# ADC.net
KiCad netlist of a schematic drawn in Altium Designer
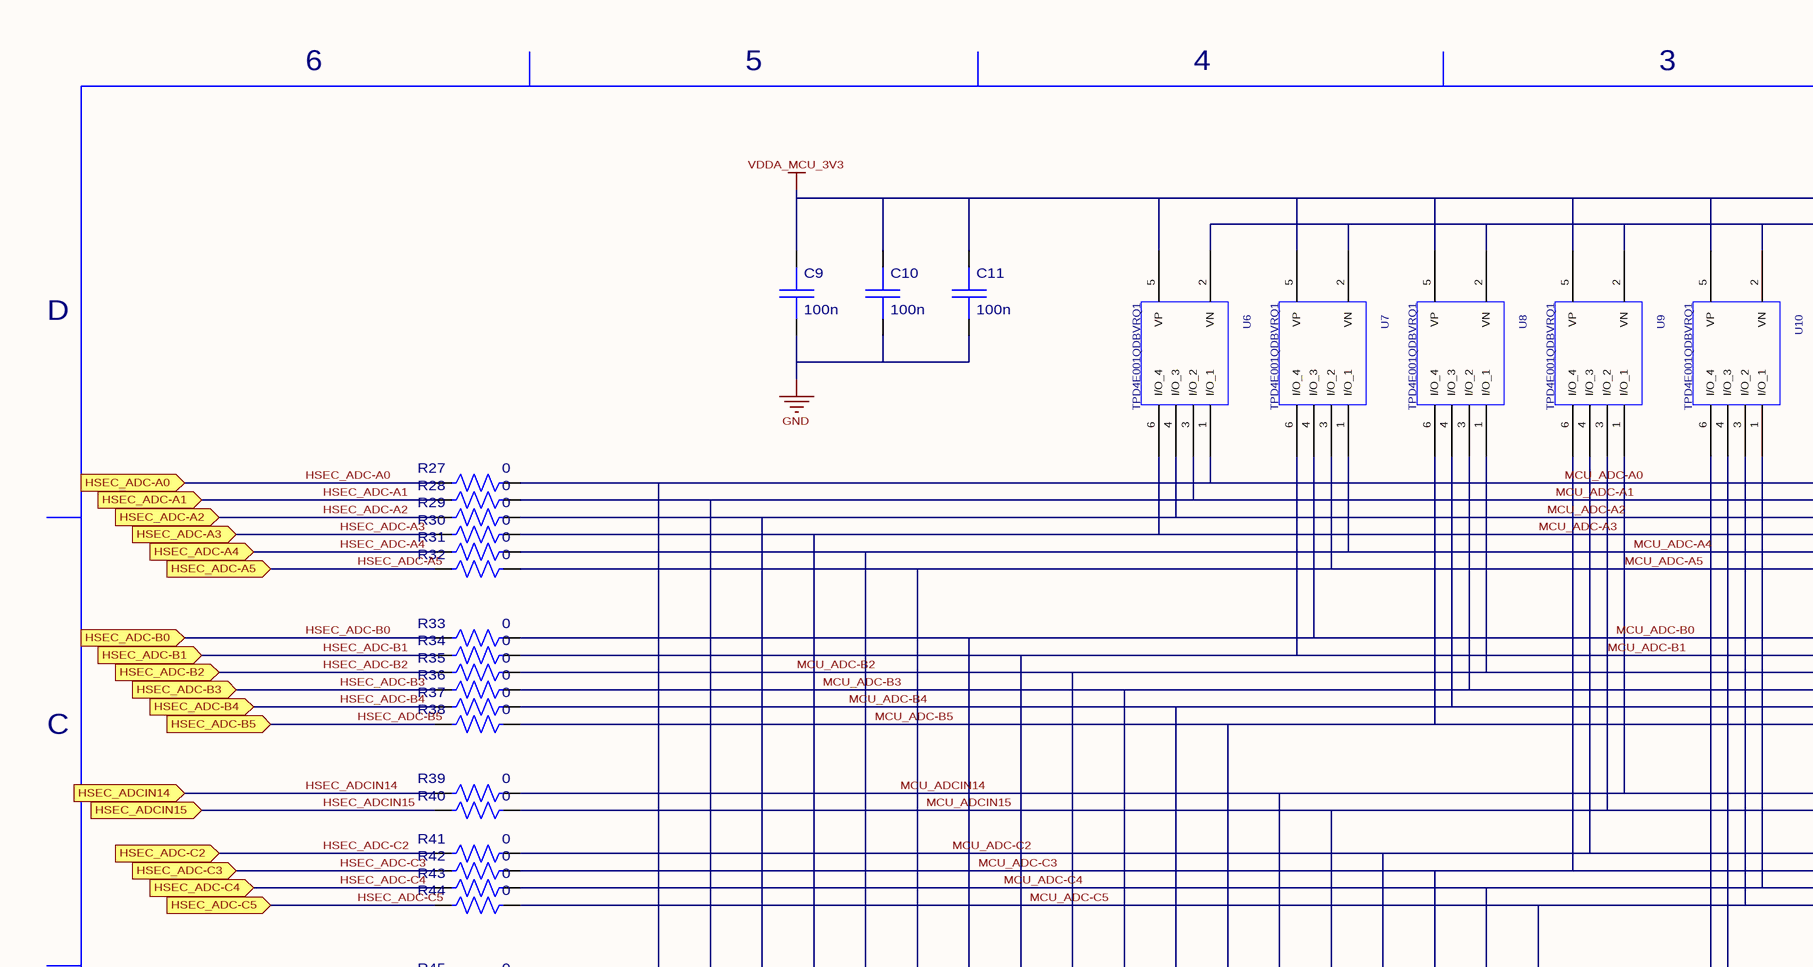
[diagram p0: ADC.SchDoc, top left]
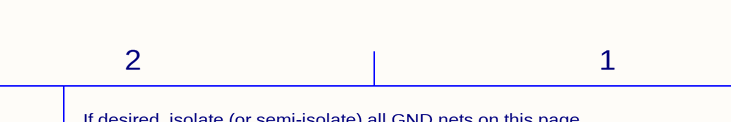
[diagram p1: ADC.SchDoc, top right]
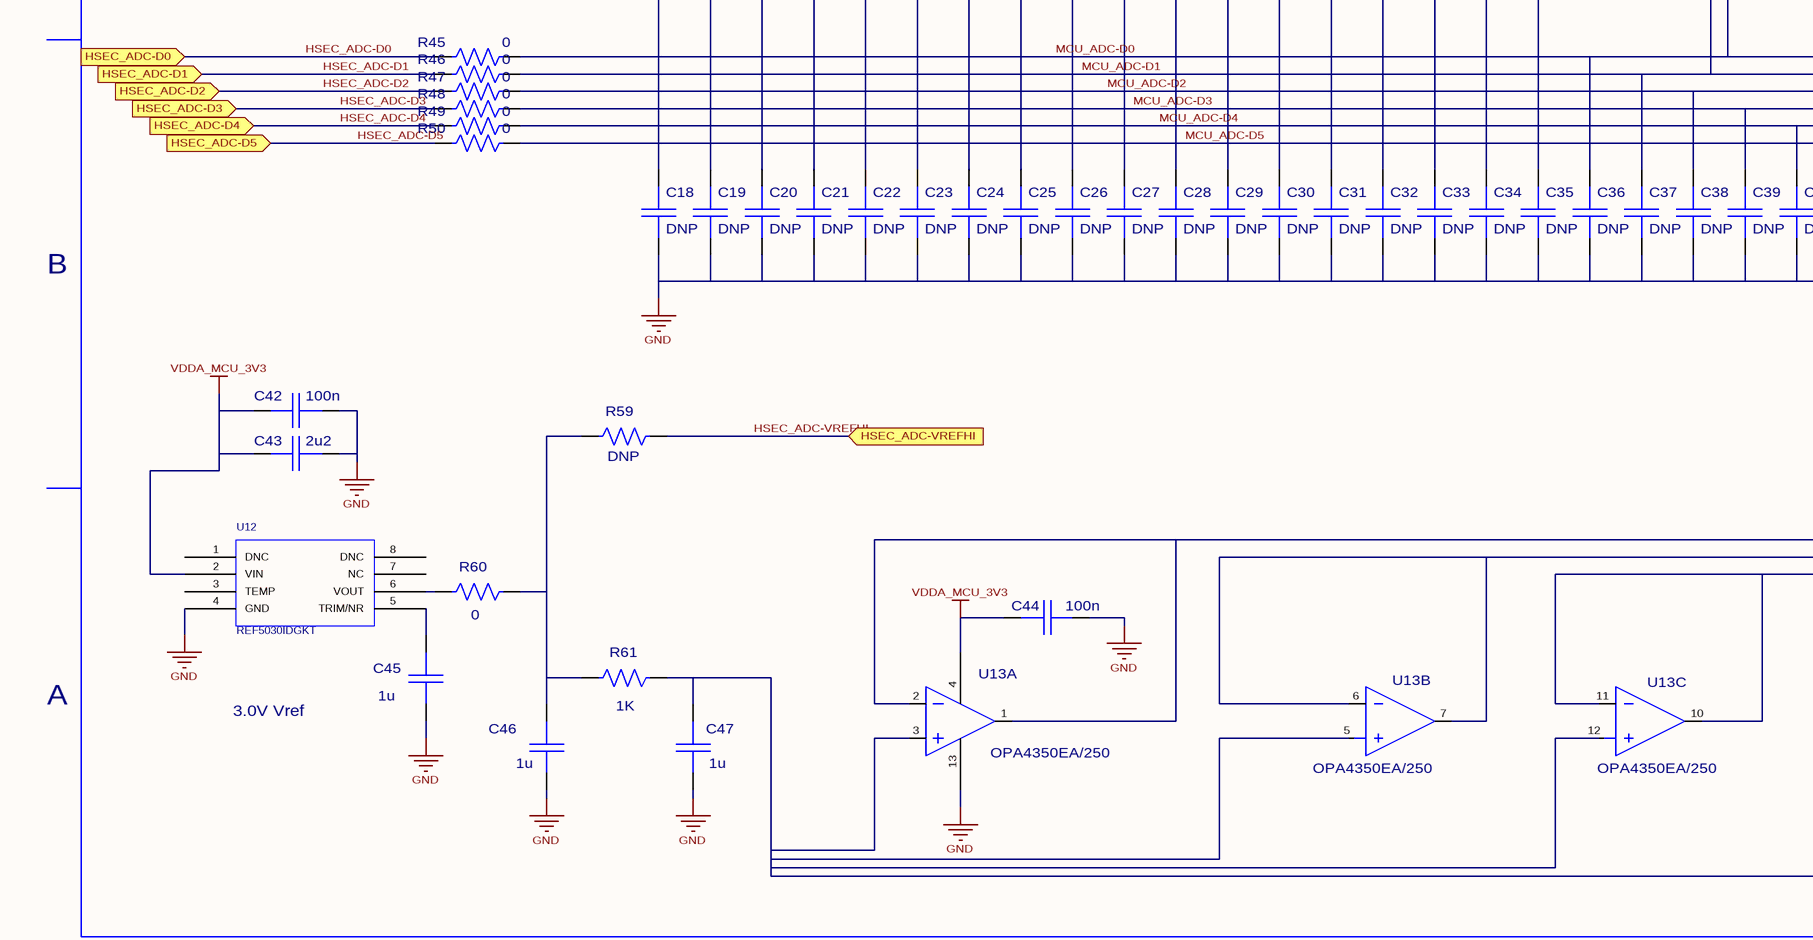
[diagram p2: ADC.SchDoc, bottom left]
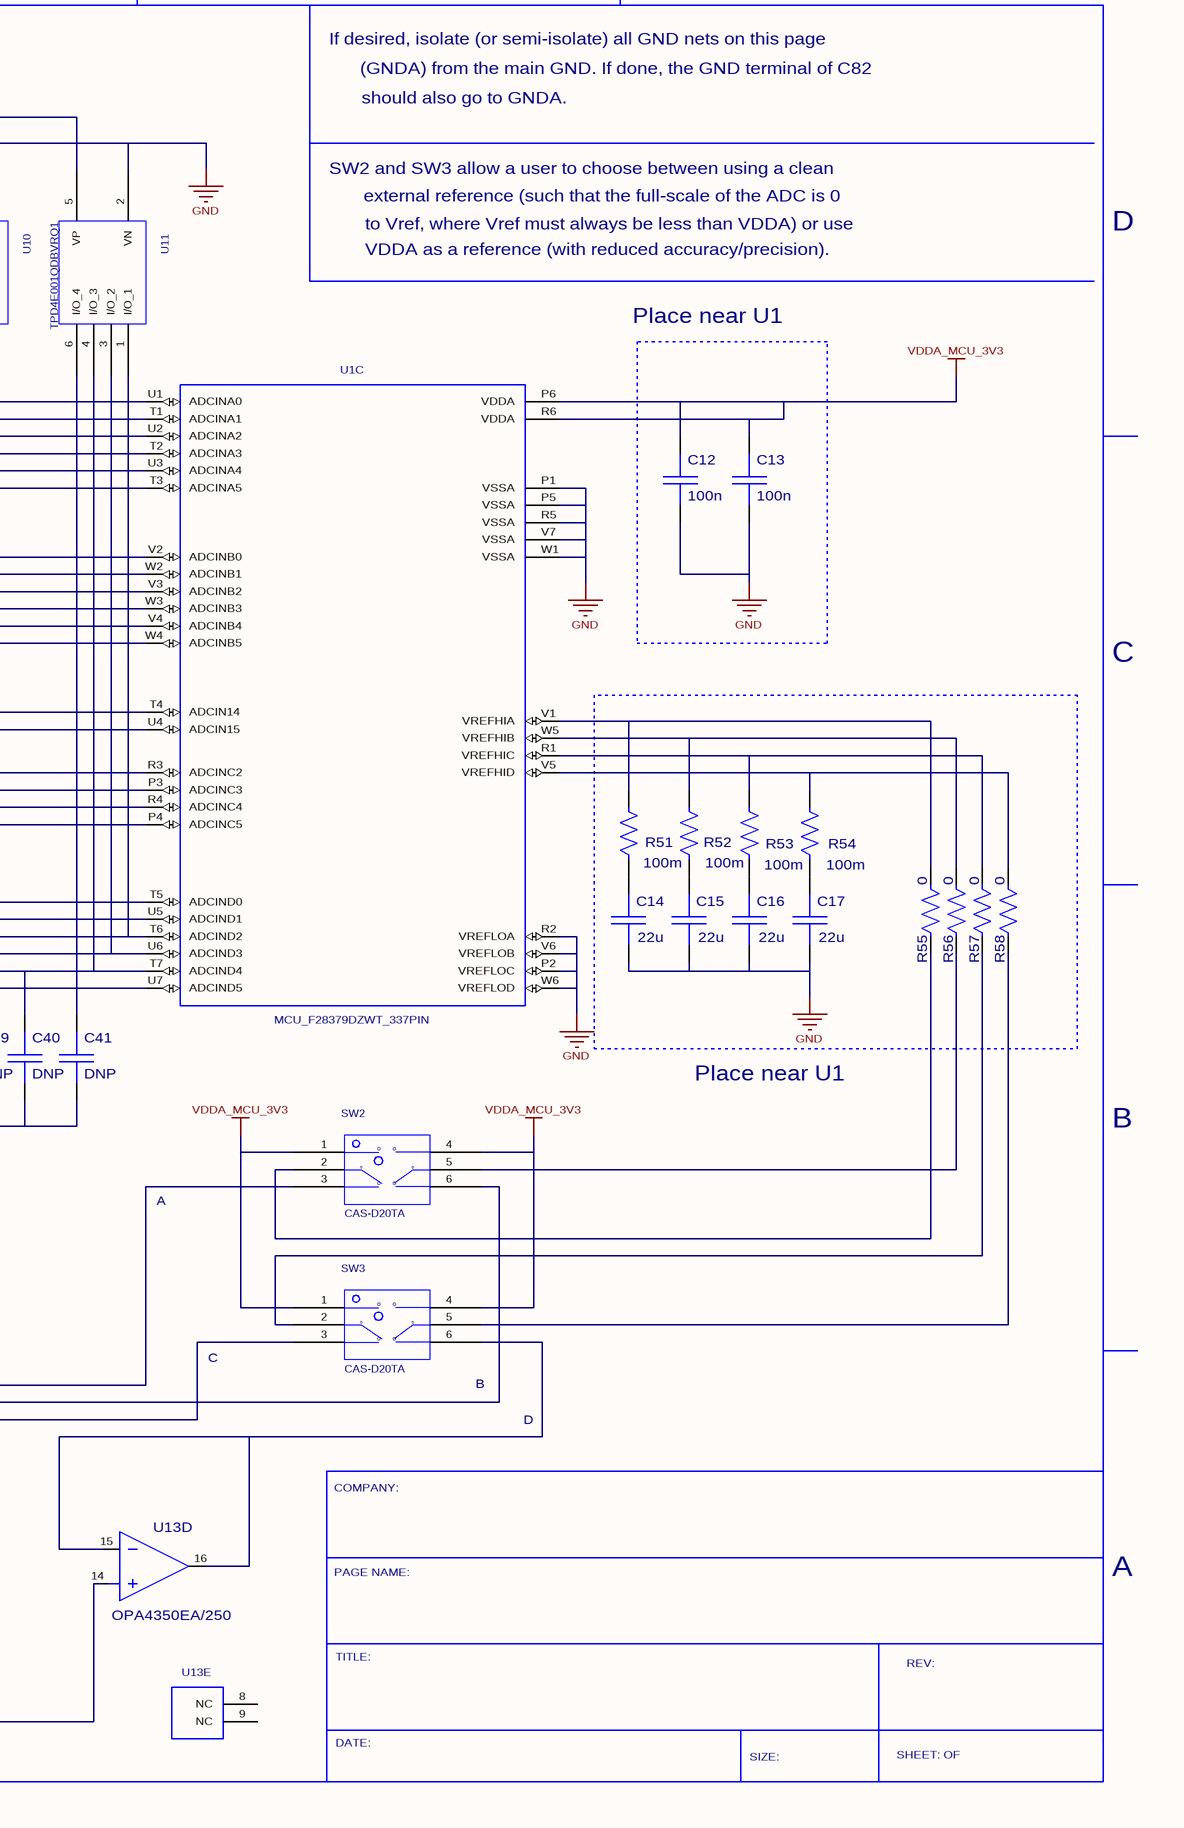
[diagram p3: ADC.SchDoc, bottom right]

(export (version "E")
  (design (tool "Eeschema 10.0.6"))
  (components
    (comp (ref "C9")
      (value "100n")
      (footprint "C0402")
      (description "CAP CER 16V 10% X7R 0402")
      (fields (field (name "Comment") "C0402_16V_X7R"))
      (libsource (lib "*") (part "C0402_16V_X7R"))
    )
    (comp (ref "C10")
      (value "100n")
      (footprint "C0402")
      (description "CAP CER 16V 10% X7R 0402")
      (fields (field (name "Comment") "C0402_16V_X7R"))
      (libsource (lib "*") (part "C0402_16V_X7R"))
    )
    (comp (ref "C11")
      (value "100n")
      (footprint "C0402")
      (description "CAP CER 16V 10% X7R 0402")
      (fields (field (name "Comment") "C0402_16V_X7R"))
      (libsource (lib "*") (part "C0402_16V_X7R"))
    )
    (comp (ref "C12")
      (value "100n")
      (footprint "C0402")
      (description "CAP CER 16V 10% X7R 0402")
      (fields (field (name "Comment") "C0402_16V_X7R"))
      (libsource (lib "*") (part "C0402_16V_X7R"))
    )
    (comp (ref "C13")
      (value "100n")
      (footprint "C0402")
      (description "CAP CER 16V 10% X7R 0402")
      (fields (field (name "Comment") "C0402_16V_X7R"))
      (libsource (lib "*") (part "C0402_16V_X7R"))
    )
    (comp (ref "C14")
      (value "22u")
      (footprint "C0805")
      (description "CAP CER 10V 20% X5R/X7S 0805")
      (fields (field (name "Comment") "C0805_16V_X7R"))
      (libsource (lib "*") (part "C0805_16V_X7R"))
    )
    (comp (ref "C15")
      (value "22u")
      (footprint "C0805")
      (description "CAP CER 10V 20% X5R/X7S 0805")
      (fields (field (name "Comment") "C0805_16V_X7R"))
      (libsource (lib "*") (part "C0805_16V_X7R"))
    )
    (comp (ref "C16")
      (value "22u")
      (footprint "C0805")
      (description "CAP CER 10V 20% X5R/X7S 0805")
      (fields (field (name "Comment") "C0805_16V_X7R"))
      (libsource (lib "*") (part "C0805_16V_X7R"))
    )
    (comp (ref "C17")
      (value "22u")
      (footprint "C0805")
      (description "CAP CER 10V 20% X5R/X7S 0805")
      (fields (field (name "Comment") "C0805_16V_X7R"))
      (libsource (lib "*") (part "C0805_16V_X7R"))
    )
    (comp (ref "C18")
      (value "DNP")
      (footprint "C0603")
      (description "CAP CER 16V 10% X7R 0603")
      (fields (field (name "Comment") "C0603_16V_X7R"))
      (libsource (lib "*") (part "C0603_16V_X7R"))
    )
    (comp (ref "C19")
      (value "DNP")
      (footprint "C0603")
      (description "CAP CER 16V 10% X7R 0603")
      (fields (field (name "Comment") "C0603_16V_X7R"))
      (libsource (lib "*") (part "C0603_16V_X7R"))
    )
    (comp (ref "C20")
      (value "DNP")
      (footprint "C0603")
      (description "CAP CER 16V 10% X7R 0603")
      (fields (field (name "Comment") "C0603_16V_X7R"))
      (libsource (lib "*") (part "C0603_16V_X7R"))
    )
    (comp (ref "C21")
      (value "DNP")
      (footprint "C0603")
      (description "CAP CER 16V 10% X7R 0603")
      (fields (field (name "Comment") "C0603_16V_X7R"))
      (libsource (lib "*") (part "C0603_16V_X7R"))
    )
    (comp (ref "C22")
      (value "DNP")
      (footprint "C0603")
      (description "CAP CER 16V 10% X7R 0603")
      (fields (field (name "Comment") "C0603_16V_X7R"))
      (libsource (lib "*") (part "C0603_16V_X7R"))
    )
    (comp (ref "C23")
      (value "DNP")
      (footprint "C0603")
      (description "CAP CER 16V 10% X7R 0603")
      (fields (field (name "Comment") "C0603_16V_X7R"))
      (libsource (lib "*") (part "C0603_16V_X7R"))
    )
    (comp (ref "C24")
      (value "DNP")
      (footprint "C0603")
      (description "CAP CER 16V 10% X7R 0603")
      (fields (field (name "Comment") "C0603_16V_X7R"))
      (libsource (lib "*") (part "C0603_16V_X7R"))
    )
    (comp (ref "C25")
      (value "DNP")
      (footprint "C0603")
      (description "CAP CER 16V 10% X7R 0603")
      (fields (field (name "Comment") "C0603_16V_X7R"))
      (libsource (lib "*") (part "C0603_16V_X7R"))
    )
    (comp (ref "C26")
      (value "DNP")
      (footprint "C0603")
      (description "CAP CER 16V 10% X7R 0603")
      (fields (field (name "Comment") "C0603_16V_X7R"))
      (libsource (lib "*") (part "C0603_16V_X7R"))
    )
    (comp (ref "C27")
      (value "DNP")
      (footprint "C0603")
      (description "CAP CER 16V 10% X7R 0603")
      (fields (field (name "Comment") "C0603_16V_X7R"))
      (libsource (lib "*") (part "C0603_16V_X7R"))
    )
    (comp (ref "C28")
      (value "DNP")
      (footprint "C0603")
      (description "CAP CER 16V 10% X7R 0603")
      (fields (field (name "Comment") "C0603_16V_X7R"))
      (libsource (lib "*") (part "C0603_16V_X7R"))
    )
    (comp (ref "C29")
      (value "DNP")
      (footprint "C0603")
      (description "CAP CER 16V 10% X7R 0603")
      (fields (field (name "Comment") "C0603_16V_X7R"))
      (libsource (lib "*") (part "C0603_16V_X7R"))
    )
    (comp (ref "C30")
      (value "DNP")
      (footprint "C0603")
      (description "CAP CER 16V 10% X7R 0603")
      (fields (field (name "Comment") "C0603_16V_X7R"))
      (libsource (lib "*") (part "C0603_16V_X7R"))
    )
    (comp (ref "C31")
      (value "DNP")
      (footprint "C0603")
      (description "CAP CER 16V 10% X7R 0603")
      (fields (field (name "Comment") "C0603_16V_X7R"))
      (libsource (lib "*") (part "C0603_16V_X7R"))
    )
    (comp (ref "C32")
      (value "DNP")
      (footprint "C0603")
      (description "CAP CER 16V 10% X7R 0603")
      (fields (field (name "Comment") "C0603_16V_X7R"))
      (libsource (lib "*") (part "C0603_16V_X7R"))
    )
    (comp (ref "C33")
      (value "DNP")
      (footprint "C0603")
      (description "CAP CER 16V 10% X7R 0603")
      (fields (field (name "Comment") "C0603_16V_X7R"))
      (libsource (lib "*") (part "C0603_16V_X7R"))
    )
    (comp (ref "C34")
      (value "DNP")
      (footprint "C0603")
      (description "CAP CER 16V 10% X7R 0603")
      (fields (field (name "Comment") "C0603_16V_X7R"))
      (libsource (lib "*") (part "C0603_16V_X7R"))
    )
    (comp (ref "C35")
      (value "DNP")
      (footprint "C0603")
      (description "CAP CER 16V 10% X7R 0603")
      (fields (field (name "Comment") "C0603_16V_X7R"))
      (libsource (lib "*") (part "C0603_16V_X7R"))
    )
    (comp (ref "C36")
      (value "DNP")
      (footprint "C0603")
      (description "CAP CER 16V 10% X7R 0603")
      (fields (field (name "Comment") "C0603_16V_X7R"))
      (libsource (lib "*") (part "C0603_16V_X7R"))
    )
    (comp (ref "C37")
      (value "DNP")
      (footprint "C0603")
      (description "CAP CER 16V 10% X7R 0603")
      (fields (field (name "Comment") "C0603_16V_X7R"))
      (libsource (lib "*") (part "C0603_16V_X7R"))
    )
    (comp (ref "C38")
      (value "DNP")
      (footprint "C0603")
      (description "CAP CER 16V 10% X7R 0603")
      (fields (field (name "Comment") "C0603_16V_X7R"))
      (libsource (lib "*") (part "C0603_16V_X7R"))
    )
    (comp (ref "C39")
      (value "DNP")
      (footprint "C0603")
      (description "CAP CER 16V 10% X7R 0603")
      (fields (field (name "Comment") "C0603_16V_X7R"))
      (libsource (lib "*") (part "C0603_16V_X7R"))
    )
    (comp (ref "C40")
      (value "DNP")
      (footprint "C0603")
      (description "CAP CER 16V 10% X7R 0603")
      (fields (field (name "Comment") "C0603_16V_X7R"))
      (libsource (lib "*") (part "C0603_16V_X7R"))
    )
    (comp (ref "C41")
      (value "DNP")
      (footprint "C0603")
      (description "CAP CER 16V 10% X7R 0603")
      (fields (field (name "Comment") "C0603_16V_X7R"))
      (libsource (lib "*") (part "C0603_16V_X7R"))
    )
    (comp (ref "C42")
      (value "100n")
      (footprint "C0402")
      (description "CAP CER 16V 10% X7R 0402")
      (fields (field (name "Comment") "C0402_16V_X7R"))
      (libsource (lib "*") (part "C0402_16V_X7R"))
    )
    (comp (ref "C43")
      (value "2u2")
      (footprint "C0603")
      (description "CAP CER 10V 20% X5R 0603")
      (fields (field (name "Comment") "C0603_16V_X7R"))
      (libsource (lib "*") (part "C0603_16V_X7R"))
    )
    (comp (ref "C44")
      (value "100n")
      (footprint "C0402")
      (description "CAP CER 16V 10% X7R 0402")
      (fields (field (name "Comment") "C0402_16V_X7R"))
      (libsource (lib "*") (part "C0402_16V_X7R"))
    )
    (comp (ref "C45")
      (value "1u")
      (footprint "C0402")
      (description "CAP CER 6.3V 10% X7R 0402")
      (fields (field (name "Comment") "C0402_16V_X7R"))
      (libsource (lib "*") (part "C0402_16V_X7R"))
    )
    (comp (ref "C46")
      (value "1u")
      (footprint "C0402")
      (description "CAP CER 6.3V 10% X7R 0402")
      (fields (field (name "Comment") "C0402_16V_X7R"))
      (libsource (lib "*") (part "C0402_16V_X7R"))
    )
    (comp (ref "C47")
      (value "1u")
      (footprint "C0402")
      (description "CAP CER 6.3V 10% X7R 0402")
      (fields (field (name "Comment") "C0402_16V_X7R"))
      (libsource (lib "*") (part "C0402_16V_X7R"))
    )
    (comp (ref "R27")
      (value "0")
      (footprint "R0603")
      (description "RES 1/10W 5% 0603 SMD")
      (fields (field (name "Comment") "R0603_5%"))
      (libsource (lib "*") (part "R0603_5%"))
    )
    (comp (ref "R28")
      (value "0")
      (footprint "R0603")
      (description "RES 1/10W 5% 0603 SMD")
      (fields (field (name "Comment") "R0603_5%"))
      (libsource (lib "*") (part "R0603_5%"))
    )
    (comp (ref "R29")
      (value "0")
      (footprint "R0603")
      (description "RES 1/10W 5% 0603 SMD")
      (fields (field (name "Comment") "R0603_5%"))
      (libsource (lib "*") (part "R0603_5%"))
    )
    (comp (ref "R30")
      (value "0")
      (footprint "R0603")
      (description "RES 1/10W 5% 0603 SMD")
      (fields (field (name "Comment") "R0603_5%"))
      (libsource (lib "*") (part "R0603_5%"))
    )
    (comp (ref "R31")
      (value "0")
      (footprint "R0603")
      (description "RES 1/10W 5% 0603 SMD")
      (fields (field (name "Comment") "R0603_5%"))
      (libsource (lib "*") (part "R0603_5%"))
    )
    (comp (ref "R32")
      (value "0")
      (footprint "R0603")
      (description "RES 1/10W 5% 0603 SMD")
      (fields (field (name "Comment") "R0603_5%"))
      (libsource (lib "*") (part "R0603_5%"))
    )
    (comp (ref "R33")
      (value "0")
      (footprint "R0603")
      (description "RES 1/10W 5% 0603 SMD")
      (fields (field (name "Comment") "R0603_5%"))
      (libsource (lib "*") (part "R0603_5%"))
    )
    (comp (ref "R34")
      (value "0")
      (footprint "R0603")
      (description "RES 1/10W 5% 0603 SMD")
      (fields (field (name "Comment") "R0603_5%"))
      (libsource (lib "*") (part "R0603_5%"))
    )
    (comp (ref "R35")
      (value "0")
      (footprint "R0603")
      (description "RES 1/10W 5% 0603 SMD")
      (fields (field (name "Comment") "R0603_5%"))
      (libsource (lib "*") (part "R0603_5%"))
    )
    (comp (ref "R36")
      (value "0")
      (footprint "R0603")
      (description "RES 1/10W 5% 0603 SMD")
      (fields (field (name "Comment") "R0603_5%"))
      (libsource (lib "*") (part "R0603_5%"))
    )
    (comp (ref "R37")
      (value "0")
      (footprint "R0603")
      (description "RES 1/10W 5% 0603 SMD")
      (fields (field (name "Comment") "R0603_5%"))
      (libsource (lib "*") (part "R0603_5%"))
    )
    (comp (ref "R38")
      (value "0")
      (footprint "R0603")
      (description "RES 1/10W 5% 0603 SMD")
      (fields (field (name "Comment") "R0603_5%"))
      (libsource (lib "*") (part "R0603_5%"))
    )
    (comp (ref "R39")
      (value "0")
      (footprint "R0603")
      (description "RES 1/10W 5% 0603 SMD")
      (fields (field (name "Comment") "R0603_5%"))
      (libsource (lib "*") (part "R0603_5%"))
    )
    (comp (ref "R40")
      (value "0")
      (footprint "R0603")
      (description "RES 1/10W 5% 0603 SMD")
      (fields (field (name "Comment") "R0603_5%"))
      (libsource (lib "*") (part "R0603_5%"))
    )
    (comp (ref "R41")
      (value "0")
      (footprint "R0603")
      (description "RES 1/10W 5% 0603 SMD")
      (fields (field (name "Comment") "R0603_5%"))
      (libsource (lib "*") (part "R0603_5%"))
    )
    (comp (ref "R42")
      (value "0")
      (footprint "R0603")
      (description "RES 1/10W 5% 0603 SMD")
      (fields (field (name "Comment") "R0603_5%"))
      (libsource (lib "*") (part "R0603_5%"))
    )
    (comp (ref "R43")
      (value "0")
      (footprint "R0603")
      (description "RES 1/10W 5% 0603 SMD")
      (fields (field (name "Comment") "R0603_5%"))
      (libsource (lib "*") (part "R0603_5%"))
    )
    (comp (ref "R44")
      (value "0")
      (footprint "R0603")
      (description "RES 1/10W 5% 0603 SMD")
      (fields (field (name "Comment") "R0603_5%"))
      (libsource (lib "*") (part "R0603_5%"))
    )
    (comp (ref "R45")
      (value "0")
      (footprint "R0603")
      (description "RES 1/10W 5% 0603 SMD")
      (fields (field (name "Comment") "R0603_5%"))
      (libsource (lib "*") (part "R0603_5%"))
    )
    (comp (ref "R46")
      (value "0")
      (footprint "R0603")
      (description "RES 1/10W 5% 0603 SMD")
      (fields (field (name "Comment") "R0603_5%"))
      (libsource (lib "*") (part "R0603_5%"))
    )
    (comp (ref "R47")
      (value "0")
      (footprint "R0603")
      (description "RES 1/10W 5% 0603 SMD")
      (fields (field (name "Comment") "R0603_5%"))
      (libsource (lib "*") (part "R0603_5%"))
    )
    (comp (ref "R48")
      (value "0")
      (footprint "R0603")
      (description "RES 1/10W 5% 0603 SMD")
      (fields (field (name "Comment") "R0603_5%"))
      (libsource (lib "*") (part "R0603_5%"))
    )
    (comp (ref "R49")
      (value "0")
      (footprint "R0603")
      (description "RES 1/10W 5% 0603 SMD")
      (fields (field (name "Comment") "R0603_5%"))
      (libsource (lib "*") (part "R0603_5%"))
    )
    (comp (ref "R50")
      (value "0")
      (footprint "R0603")
      (description "RES 1/10W 5% 0603 SMD")
      (fields (field (name "Comment") "R0603_5%"))
      (libsource (lib "*") (part "R0603_5%"))
    )
    (comp (ref "R51")
      (value "100m")
      (footprint "R0603")
      (description "RES 1/10W 5% 0603 SMD")
      (fields (field (name "Comment") "R0603_5%"))
      (libsource (lib "*") (part "R0603_5%"))
    )
    (comp (ref "R52")
      (value "100m")
      (footprint "R0603")
      (description "RES 1/10W 5% 0603 SMD")
      (fields (field (name "Comment") "R0603_5%"))
      (libsource (lib "*") (part "R0603_5%"))
    )
    (comp (ref "R53")
      (value "100m")
      (footprint "R0603")
      (description "RES 1/10W 5% 0603 SMD")
      (fields (field (name "Comment") "R0603_5%"))
      (libsource (lib "*") (part "R0603_5%"))
    )
    (comp (ref "R54")
      (value "100m")
      (footprint "R0603")
      (description "RES 1/10W 5% 0603 SMD")
      (fields (field (name "Comment") "R0603_5%"))
      (libsource (lib "*") (part "R0603_5%"))
    )
    (comp (ref "R55")
      (value "0")
      (footprint "R0402")
      (description "RES 1/16W 5% 0402 SMD")
      (fields (field (name "Comment") "R0402_5%"))
      (libsource (lib "*") (part "R0402_5%"))
    )
    (comp (ref "R56")
      (value "0")
      (footprint "R0402")
      (description "RES 1/16W 5% 0402 SMD")
      (fields (field (name "Comment") "R0402_5%"))
      (libsource (lib "*") (part "R0402_5%"))
    )
    (comp (ref "R57")
      (value "0")
      (footprint "R0402")
      (description "RES 1/16W 5% 0402 SMD")
      (fields (field (name "Comment") "R0402_5%"))
      (libsource (lib "*") (part "R0402_5%"))
    )
    (comp (ref "R58")
      (value "0")
      (footprint "R0402")
      (description "RES 1/16W 5% 0402 SMD")
      (fields (field (name "Comment") "R0402_5%"))
      (libsource (lib "*") (part "R0402_5%"))
    )
    (comp (ref "R59")
      (value "DNP")
      (footprint "R0603")
      (description "RES 1/10W 5% 0603 SMD")
      (fields (field (name "Comment") "R0603_5%"))
      (libsource (lib "*") (part "R0603_5%"))
    )
    (comp (ref "R60")
      (value "0")
      (footprint "R0603")
      (description "RES 1/10W 5% 0603 SMD")
      (fields (field (name "Comment") "R0603_5%"))
      (libsource (lib "*") (part "R0603_5%"))
    )
    (comp (ref "R61")
      (value "1K")
      (footprint "R0603")
      (description "RES 1/10W 5% 0603 SMD")
      (fields (field (name "Comment") "R0603_5%"))
      (libsource (lib "*") (part "R0603_5%"))
    )
    (comp (ref "SW2")
      (value "CAS-D20TA")
      (footprint "SWITCH_CAS-D20TA")
      (description "Switch SPDT, 2 position")
      (fields (field (name "MANUFACTURER") "Copal Electronics") (field (name "Comment") "SWITCH_CAS-D20TA"))
      (libsource (lib "*") (part "SWITCH_CAS-D20TA"))
    )
    (comp (ref "SW3")
      (value "CAS-D20TA")
      (footprint "SWITCH_CAS-D20TA")
      (description "Switch SPDT, 2 position")
      (fields (field (name "MANUFACTURER") "Copal Electronics") (field (name "Comment") "SWITCH_CAS-D20TA"))
      (libsource (lib "*") (part "SWITCH_CAS-D20TA"))
    )
    (comp (ref "U1")
      (value "MCU_F28379DZWT_337PIN")
      (footprint "TI_ZWT_337BGA")
      (description "MCU F2837x 337pin ZWT BGA")
      (fields (field (name "PART NUMBER") "TMS320F28379DZWT"))
      (libsource (lib "*") (part "MCU_F28379DZWT_337PIN"))
    )
    (comp (ref "U6")
      (value "TPD4E001QDBVRQ1")
      (footprint "SOT-23-6")
      (description "TVS 4-ch UniDir Diode Array: VCC & GND prot, 11V brkdwn")
      (fields (field (name "MANUFACTURER") "Texas Instruments"))
      (libsource (lib "*") (part "TPD4E001QDBVRQ1"))
    )
    (comp (ref "U7")
      (value "TPD4E001QDBVRQ1")
      (footprint "SOT-23-6")
      (description "TVS 4-ch UniDir Diode Array: VCC & GND prot, 11V brkdwn")
      (fields (field (name "MANUFACTURER") "Texas Instruments"))
      (libsource (lib "*") (part "TPD4E001QDBVRQ1"))
    )
    (comp (ref "U8")
      (value "TPD4E001QDBVRQ1")
      (footprint "SOT-23-6")
      (description "TVS 4-ch UniDir Diode Array: VCC & GND prot, 11V brkdwn")
      (fields (field (name "MANUFACTURER") "Texas Instruments"))
      (libsource (lib "*") (part "TPD4E001QDBVRQ1"))
    )
    (comp (ref "U9")
      (value "TPD4E001QDBVRQ1")
      (footprint "SOT-23-6")
      (description "TVS 4-ch UniDir Diode Array: VCC & GND prot, 11V brkdwn")
      (fields (field (name "MANUFACTURER") "Texas Instruments"))
      (libsource (lib "*") (part "TPD4E001QDBVRQ1"))
    )
    (comp (ref "U10")
      (value "TPD4E001QDBVRQ1")
      (footprint "SOT-23-6")
      (description "TVS 4-ch UniDir Diode Array: VCC & GND prot, 11V brkdwn")
      (fields (field (name "MANUFACTURER") "Texas Instruments"))
      (libsource (lib "*") (part "TPD4E001QDBVRQ1"))
    )
    (comp (ref "U11")
      (value "TPD4E001QDBVRQ1")
      (footprint "SOT-23-6")
      (description "TVS 4-ch UniDir Diode Array: VCC & GND prot, 11V brkdwn")
      (fields (field (name "MANUFACTURER") "Texas Instruments"))
      (libsource (lib "*") (part "TPD4E001QDBVRQ1"))
    )
    (comp (ref "U12")
      (value "REF5030IDGKT")
      (footprint "MSOP8_DGK")
      (description "IC, 3.0V Vref, 0.05%, 8DGK")
      (fields (field (name "Comment") "IC_REF_REF5030IDGK"))
      (libsource (lib "*") (part "IC_REF_REF5030IDGK"))
    )
    (comp (ref "U13")
      (value "OPA4350EA/250")
      (footprint "SSOP16_DBQ")
      (description "IC OPAMP GP R-R 38MHZ QUAD 16DBQ")
      (fields (field (name "PART NUMBER") "OPA4350EA/250") (field (name "Comment") "IC_OPA_OPA4350EA"))
      (libsource (lib "*") (part "IC_OPA_OPA4350EA"))
    )
  )
  (nets
    (net (code "1") (name "/HSEC_ADC-A0") (class "Default")
      (node (ref "R27") (pin "1") (pinfunction "1_1") (pintype "passive"))
    )
    (net (code "2") (name "/HSEC_ADC-A1") (class "Default")
      (node (ref "R28") (pin "1") (pinfunction "1_1") (pintype "passive"))
    )
    (net (code "3") (name "/HSEC_ADC-A2") (class "Default")
      (node (ref "R29") (pin "1") (pinfunction "1_1") (pintype "passive"))
    )
    (net (code "4") (name "/HSEC_ADC-A3") (class "Default")
      (node (ref "R30") (pin "1") (pinfunction "1_1") (pintype "passive"))
    )
    (net (code "5") (name "/HSEC_ADC-A4") (class "Default")
      (node (ref "R31") (pin "1") (pinfunction "1_1") (pintype "passive"))
    )
    (net (code "6") (name "/HSEC_ADC-A5") (class "Default")
      (node (ref "R32") (pin "1") (pinfunction "1_1") (pintype "passive"))
    )
    (net (code "7") (name "/HSEC_ADC-B0") (class "Default")
      (node (ref "R33") (pin "1") (pinfunction "1_1") (pintype "passive"))
    )
    (net (code "8") (name "/HSEC_ADC-B1") (class "Default")
      (node (ref "R34") (pin "1") (pinfunction "1_1") (pintype "passive"))
    )
    (net (code "9") (name "/HSEC_ADC-B2") (class "Default")
      (node (ref "R35") (pin "1") (pinfunction "1_1") (pintype "passive"))
    )
    (net (code "10") (name "/HSEC_ADC-B3") (class "Default")
      (node (ref "R36") (pin "1") (pinfunction "1_1") (pintype "passive"))
    )
    (net (code "11") (name "/HSEC_ADC-B4") (class "Default")
      (node (ref "R37") (pin "1") (pinfunction "1_1") (pintype "passive"))
    )
    (net (code "12") (name "/HSEC_ADC-B5") (class "Default")
      (node (ref "R38") (pin "1") (pinfunction "1_1") (pintype "passive"))
    )
    (net (code "13") (name "/HSEC_ADC-C2") (class "Default")
      (node (ref "R41") (pin "1") (pinfunction "1_1") (pintype "passive"))
    )
    (net (code "14") (name "/HSEC_ADC-C3") (class "Default")
      (node (ref "R42") (pin "1") (pinfunction "1_1") (pintype "passive"))
    )
    (net (code "15") (name "/HSEC_ADC-C4") (class "Default")
      (node (ref "R43") (pin "1") (pinfunction "1_1") (pintype "passive"))
    )
    (net (code "16") (name "/HSEC_ADC-C5") (class "Default")
      (node (ref "R44") (pin "1") (pinfunction "1_1") (pintype "passive"))
    )
    (net (code "17") (name "/HSEC_ADC-D0") (class "Default")
      (node (ref "R45") (pin "1") (pinfunction "1_1") (pintype "passive"))
    )
    (net (code "18") (name "/HSEC_ADC-D1") (class "Default")
      (node (ref "R46") (pin "1") (pinfunction "1_1") (pintype "passive"))
    )
    (net (code "19") (name "/HSEC_ADC-D2") (class "Default")
      (node (ref "R47") (pin "1") (pinfunction "1_1") (pintype "passive"))
    )
    (net (code "20") (name "/HSEC_ADC-D3") (class "Default")
      (node (ref "R48") (pin "1") (pinfunction "1_1") (pintype "passive"))
    )
    (net (code "21") (name "/HSEC_ADC-D4") (class "Default")
      (node (ref "R49") (pin "1") (pinfunction "1_1") (pintype "passive"))
    )
    (net (code "22") (name "/HSEC_ADC-D5") (class "Default")
      (node (ref "R50") (pin "1") (pinfunction "1_1") (pintype "passive"))
    )
    (net (code "23") (name "/HSEC_ADC-VREFHI") (class "Default")
      (node (ref "R59") (pin "2") (pinfunction "2_2") (pintype "passive"))
    )
    (net (code "24") (name "/HSEC_ADCIN14") (class "Default")
      (node (ref "R39") (pin "1") (pinfunction "1_1") (pintype "passive"))
    )
    (net (code "25") (name "/HSEC_ADCIN15") (class "Default")
      (node (ref "R40") (pin "1") (pinfunction "1_1") (pintype "passive"))
    )
    (net (code "26") (name "/MCU_ADC-A0") (class "Default")
      (node (ref "C18") (pin "2") (pinfunction "2_2") (pintype "passive"))
      (node (ref "R27") (pin "2") (pinfunction "2_2") (pintype "passive"))
      (node (ref "U1") (pin "U1") (pinfunction "ADCINA0_U1") (pintype "bidirectional"))
      (node (ref "U6") (pin "1") (pinfunction "I/O_1_1") (pintype "passive"))
    )
    (net (code "27") (name "/MCU_ADC-A1") (class "Default")
      (node (ref "C19") (pin "2") (pinfunction "2_2") (pintype "passive"))
      (node (ref "R28") (pin "2") (pinfunction "2_2") (pintype "passive"))
      (node (ref "U1") (pin "T1") (pinfunction "ADCINA1_T1") (pintype "bidirectional"))
      (node (ref "U6") (pin "3") (pinfunction "I/O_2_3") (pintype "passive"))
    )
    (net (code "28") (name "/MCU_ADC-A2") (class "Default")
      (node (ref "C20") (pin "2") (pinfunction "2_2") (pintype "passive"))
      (node (ref "R29") (pin "2") (pinfunction "2_2") (pintype "passive"))
      (node (ref "U1") (pin "U2") (pinfunction "ADCINA2_U2") (pintype "bidirectional"))
      (node (ref "U6") (pin "4") (pinfunction "I/O_3_4") (pintype "passive"))
    )
    (net (code "29") (name "/MCU_ADC-A3") (class "Default")
      (node (ref "C21") (pin "2") (pinfunction "2_2") (pintype "passive"))
      (node (ref "R30") (pin "2") (pinfunction "2_2") (pintype "passive"))
      (node (ref "U1") (pin "T2") (pinfunction "ADCINA3_T2") (pintype "bidirectional"))
      (node (ref "U6") (pin "6") (pinfunction "I/O_4_6") (pintype "passive"))
    )
    (net (code "30") (name "/MCU_ADC-A4") (class "Default")
      (node (ref "C22") (pin "2") (pinfunction "2_2") (pintype "passive"))
      (node (ref "R31") (pin "2") (pinfunction "2_2") (pintype "passive"))
      (node (ref "U1") (pin "U3") (pinfunction "ADCINA4_U3") (pintype "bidirectional"))
      (node (ref "U7") (pin "1") (pinfunction "I/O_1_1") (pintype "passive"))
    )
    (net (code "31") (name "/MCU_ADC-A5") (class "Default")
      (node (ref "C23") (pin "2") (pinfunction "2_2") (pintype "passive"))
      (node (ref "C30") (pin "2") (pinfunction "2_2") (pintype "passive"))
      (node (ref "R32") (pin "2") (pinfunction "2_2") (pintype "passive"))
      (node (ref "R39") (pin "2") (pinfunction "2_2") (pintype "passive"))
      (node (ref "U1") (pin "T3") (pinfunction "ADCINA5_T3") (pintype "bidirectional"))
      (node (ref "U1") (pin "T4") (pinfunction "ADCIN14_T4") (pintype "bidirectional"))
      (node (ref "U7") (pin "3") (pinfunction "I/O_2_3") (pintype "passive"))
      (node (ref "U9") (pin "1") (pinfunction "I/O_1_1") (pintype "passive"))
    )
    (net (code "32") (name "/MCU_ADC-B0") (class "Default")
      (node (ref "C24") (pin "2") (pinfunction "2_2") (pintype "passive"))
      (node (ref "R33") (pin "2") (pinfunction "2_2") (pintype "passive"))
      (node (ref "U1") (pin "V2") (pinfunction "ADCINB0_V2") (pintype "bidirectional"))
      (node (ref "U7") (pin "4") (pinfunction "I/O_3_4") (pintype "passive"))
    )
    (net (code "33") (name "/MCU_ADC-B1") (class "Default")
      (node (ref "C25") (pin "2") (pinfunction "2_2") (pintype "passive"))
      (node (ref "C31") (pin "2") (pinfunction "2_2") (pintype "passive"))
      (node (ref "R34") (pin "2") (pinfunction "2_2") (pintype "passive"))
      (node (ref "R40") (pin "2") (pinfunction "2_2") (pintype "passive"))
      (node (ref "U1") (pin "U4") (pinfunction "ADCIN15_U4") (pintype "bidirectional"))
      (node (ref "U1") (pin "W2") (pinfunction "ADCINB1_W2") (pintype "bidirectional"))
      (node (ref "U7") (pin "6") (pinfunction "I/O_4_6") (pintype "passive"))
      (node (ref "U9") (pin "3") (pinfunction "I/O_2_3") (pintype "passive"))
    )
    (net (code "34") (name "/MCU_ADC-B2") (class "Default")
      (node (ref "C26") (pin "2") (pinfunction "2_2") (pintype "passive"))
      (node (ref "R35") (pin "2") (pinfunction "2_2") (pintype "passive"))
      (node (ref "U1") (pin "V3") (pinfunction "ADCINB2_V3") (pintype "bidirectional"))
      (node (ref "U8") (pin "1") (pinfunction "I/O_1_1") (pintype "passive"))
    )
    (net (code "35") (name "/MCU_ADC-B3") (class "Default")
      (node (ref "C27") (pin "2") (pinfunction "2_2") (pintype "passive"))
      (node (ref "R36") (pin "2") (pinfunction "2_2") (pintype "passive"))
      (node (ref "U1") (pin "W3") (pinfunction "ADCINB3_W3") (pintype "bidirectional"))
      (node (ref "U8") (pin "3") (pinfunction "I/O_2_3") (pintype "passive"))
    )
    (net (code "36") (name "/MCU_ADC-B4") (class "Default")
      (node (ref "C28") (pin "2") (pinfunction "2_2") (pintype "passive"))
      (node (ref "R37") (pin "2") (pinfunction "2_2") (pintype "passive"))
      (node (ref "U1") (pin "V4") (pinfunction "ADCINB4_V4") (pintype "bidirectional"))
      (node (ref "U8") (pin "4") (pinfunction "I/O_3_4") (pintype "passive"))
    )
    (net (code "37") (name "/MCU_ADC-B5") (class "Default")
      (node (ref "C29") (pin "2") (pinfunction "2_2") (pintype "passive"))
      (node (ref "R38") (pin "2") (pinfunction "2_2") (pintype "passive"))
      (node (ref "U1") (pin "W4") (pinfunction "ADCINB5_W4") (pintype "bidirectional"))
      (node (ref "U8") (pin "6") (pinfunction "I/O_4_6") (pintype "passive"))
    )
    (net (code "38") (name "/MCU_ADC-C2") (class "Default")
      (node (ref "C32") (pin "2") (pinfunction "2_2") (pintype "passive"))
      (node (ref "R41") (pin "2") (pinfunction "2_2") (pintype "passive"))
      (node (ref "U1") (pin "R3") (pinfunction "ADCINC2_R3") (pintype "bidirectional"))
      (node (ref "U9") (pin "4") (pinfunction "I/O_3_4") (pintype "passive"))
    )
    (net (code "39") (name "/MCU_ADC-C3") (class "Default")
      (node (ref "C33") (pin "2") (pinfunction "2_2") (pintype "passive"))
      (node (ref "R42") (pin "2") (pinfunction "2_2") (pintype "passive"))
      (node (ref "U1") (pin "P3") (pinfunction "ADCINC3_P3") (pintype "bidirectional"))
      (node (ref "U9") (pin "6") (pinfunction "I/O_4_6") (pintype "passive"))
    )
    (net (code "40") (name "/MCU_ADC-C4") (class "Default")
      (node (ref "C34") (pin "2") (pinfunction "2_2") (pintype "passive"))
      (node (ref "R43") (pin "2") (pinfunction "2_2") (pintype "passive"))
      (node (ref "U1") (pin "R4") (pinfunction "ADCINC4_R4") (pintype "bidirectional"))
      (node (ref "U10") (pin "1") (pinfunction "I/O_1_1") (pintype "passive"))
    )
    (net (code "41") (name "/MCU_ADC-C5") (class "Default")
      (node (ref "C35") (pin "2") (pinfunction "2_2") (pintype "passive"))
      (node (ref "R44") (pin "2") (pinfunction "2_2") (pintype "passive"))
      (node (ref "U1") (pin "P4") (pinfunction "ADCINC5_P4") (pintype "bidirectional"))
      (node (ref "U10") (pin "3") (pinfunction "I/O_2_3") (pintype "passive"))
    )
    (net (code "42") (name "/MCU_ADC-D0") (class "Default")
      (node (ref "C36") (pin "2") (pinfunction "2_2") (pintype "passive"))
      (node (ref "R45") (pin "2") (pinfunction "2_2") (pintype "passive"))
      (node (ref "U1") (pin "T5") (pinfunction "ADCIND0_T5") (pintype "bidirectional"))
      (node (ref "U10") (pin "4") (pinfunction "I/O_3_4") (pintype "passive"))
    )
    (net (code "43") (name "/MCU_ADC-D1") (class "Default")
      (node (ref "C37") (pin "2") (pinfunction "2_2") (pintype "passive"))
      (node (ref "R46") (pin "2") (pinfunction "2_2") (pintype "passive"))
      (node (ref "U1") (pin "U5") (pinfunction "ADCIND1_U5") (pintype "bidirectional"))
      (node (ref "U10") (pin "6") (pinfunction "I/O_4_6") (pintype "passive"))
    )
    (net (code "44") (name "/MCU_ADC-D2") (class "Default")
      (node (ref "C38") (pin "2") (pinfunction "2_2") (pintype "passive"))
      (node (ref "R47") (pin "2") (pinfunction "2_2") (pintype "passive"))
      (node (ref "U1") (pin "T6") (pinfunction "ADCIND2_T6") (pintype "bidirectional"))
      (node (ref "U11") (pin "1") (pinfunction "I/O_1_1") (pintype "passive"))
    )
    (net (code "45") (name "/MCU_ADC-D3") (class "Default")
      (node (ref "C39") (pin "2") (pinfunction "2_2") (pintype "passive"))
      (node (ref "R48") (pin "2") (pinfunction "2_2") (pintype "passive"))
      (node (ref "U1") (pin "U6") (pinfunction "ADCIND3_U6") (pintype "bidirectional"))
      (node (ref "U11") (pin "3") (pinfunction "I/O_2_3") (pintype "passive"))
    )
    (net (code "46") (name "/MCU_ADC-D4") (class "Default")
      (node (ref "C40") (pin "2") (pinfunction "2_2") (pintype "passive"))
      (node (ref "R49") (pin "2") (pinfunction "2_2") (pintype "passive"))
      (node (ref "U1") (pin "T7") (pinfunction "ADCIND4_T7") (pintype "bidirectional"))
      (node (ref "U11") (pin "4") (pinfunction "I/O_3_4") (pintype "passive"))
    )
    (net (code "47") (name "/MCU_ADC-D5") (class "Default")
      (node (ref "C41") (pin "2") (pinfunction "2_2") (pintype "passive"))
      (node (ref "R50") (pin "2") (pinfunction "2_2") (pintype "passive"))
      (node (ref "U1") (pin "U7") (pinfunction "ADCIND5_U7") (pintype "bidirectional"))
      (node (ref "U11") (pin "6") (pinfunction "I/O_4_6") (pintype "passive"))
    )
    (net (code "48") (name "GND") (class "Default")
      (node (ref "C10") (pin "1") (pinfunction "1_1") (pintype "passive"))
      (node (ref "C11") (pin "1") (pinfunction "1_1") (pintype "passive"))
      (node (ref "C12") (pin "1") (pinfunction "1_1") (pintype "passive"))
      (node (ref "C13") (pin "1") (pinfunction "1_1") (pintype "passive"))
      (node (ref "C14") (pin "1") (pinfunction "1_1") (pintype "passive"))
      (node (ref "C15") (pin "1") (pinfunction "1_1") (pintype "passive"))
      (node (ref "C16") (pin "1") (pinfunction "1_1") (pintype "passive"))
      (node (ref "C17") (pin "1") (pinfunction "1_1") (pintype "passive"))
      (node (ref "C18") (pin "1") (pinfunction "1_1") (pintype "passive"))
      (node (ref "C19") (pin "1") (pinfunction "1_1") (pintype "passive"))
      (node (ref "C20") (pin "1") (pinfunction "1_1") (pintype "passive"))
      (node (ref "C21") (pin "1") (pinfunction "1_1") (pintype "passive"))
      (node (ref "C22") (pin "1") (pinfunction "1_1") (pintype "passive"))
      (node (ref "C23") (pin "1") (pinfunction "1_1") (pintype "passive"))
      (node (ref "C24") (pin "1") (pinfunction "1_1") (pintype "passive"))
      (node (ref "C25") (pin "1") (pinfunction "1_1") (pintype "passive"))
      (node (ref "C26") (pin "1") (pinfunction "1_1") (pintype "passive"))
      (node (ref "C27") (pin "1") (pinfunction "1_1") (pintype "passive"))
      (node (ref "C28") (pin "1") (pinfunction "1_1") (pintype "passive"))
      (node (ref "C29") (pin "1") (pinfunction "1_1") (pintype "passive"))
      (node (ref "C30") (pin "1") (pinfunction "1_1") (pintype "passive"))
      (node (ref "C31") (pin "1") (pinfunction "1_1") (pintype "passive"))
      (node (ref "C32") (pin "1") (pinfunction "1_1") (pintype "passive"))
      (node (ref "C33") (pin "1") (pinfunction "1_1") (pintype "passive"))
      (node (ref "C34") (pin "1") (pinfunction "1_1") (pintype "passive"))
      (node (ref "C35") (pin "1") (pinfunction "1_1") (pintype "passive"))
      (node (ref "C36") (pin "1") (pinfunction "1_1") (pintype "passive"))
      (node (ref "C37") (pin "1") (pinfunction "1_1") (pintype "passive"))
      (node (ref "C38") (pin "1") (pinfunction "1_1") (pintype "passive"))
      (node (ref "C39") (pin "1") (pinfunction "1_1") (pintype "passive"))
      (node (ref "C40") (pin "1") (pinfunction "1_1") (pintype "passive"))
      (node (ref "C41") (pin "1") (pinfunction "1_1") (pintype "passive"))
      (node (ref "C42") (pin "2") (pinfunction "2_2") (pintype "passive"))
      (node (ref "C43") (pin "2") (pinfunction "2_2") (pintype "passive"))
      (node (ref "C44") (pin "1") (pinfunction "1_1") (pintype "passive"))
      (node (ref "C45") (pin "1") (pinfunction "1_1") (pintype "passive"))
      (node (ref "C46") (pin "1") (pinfunction "1_1") (pintype "passive"))
      (node (ref "C47") (pin "1") (pinfunction "1_1") (pintype "passive"))
      (node (ref "C9") (pin "1") (pinfunction "1_1") (pintype "passive"))
      (node (ref "U1") (pin "P1") (pinfunction "VSSA_P1") (pintype "passive"))
      (node (ref "U1") (pin "P2") (pinfunction "VREFLOC_P2") (pintype "bidirectional"))
      (node (ref "U1") (pin "P5") (pinfunction "VSSA_P5") (pintype "passive"))
      (node (ref "U1") (pin "R2") (pinfunction "VREFLOA_R2") (pintype "bidirectional"))
      (node (ref "U1") (pin "R5") (pinfunction "VSSA_R5") (pintype "passive"))
      (node (ref "U1") (pin "V6") (pinfunction "VREFLOB_V6") (pintype "bidirectional"))
      (node (ref "U1") (pin "V7") (pinfunction "VSSA_V7") (pintype "passive"))
      (node (ref "U1") (pin "W1") (pinfunction "VSSA_W1") (pintype "passive"))
      (node (ref "U1") (pin "W6") (pinfunction "VREFLOD_W6") (pintype "bidirectional"))
      (node (ref "U10") (pin "2") (pinfunction "VN_2") (pintype "power_in"))
      (node (ref "U11") (pin "2") (pinfunction "VN_2") (pintype "power_in"))
      (node (ref "U12") (pin "4") (pinfunction "GND_4") (pintype "passive"))
      (node (ref "U13") (pin "13") (pinfunction "V-_13") (pintype "passive"))
      (node (ref "U6") (pin "2") (pinfunction "VN_2") (pintype "power_in"))
      (node (ref "U7") (pin "2") (pinfunction "VN_2") (pintype "power_in"))
      (node (ref "U8") (pin "2") (pinfunction "VN_2") (pintype "power_in"))
      (node (ref "U9") (pin "2") (pinfunction "VN_2") (pintype "power_in"))
    )
    (net (code "49") (name "Net-(C14-Pad2)") (class "Default")
      (node (ref "C14") (pin "2") (pinfunction "2_2") (pintype "passive"))
      (node (ref "R51") (pin "1") (pinfunction "1_1") (pintype "passive"))
    )
    (net (code "50") (name "Net-(C15-Pad2)") (class "Default")
      (node (ref "C15") (pin "2") (pinfunction "2_2") (pintype "passive"))
      (node (ref "R52") (pin "1") (pinfunction "1_1") (pintype "passive"))
    )
    (net (code "51") (name "Net-(C16-Pad2)") (class "Default")
      (node (ref "C16") (pin "2") (pinfunction "2_2") (pintype "passive"))
      (node (ref "R53") (pin "1") (pinfunction "1_1") (pintype "passive"))
    )
    (net (code "52") (name "Net-(C17-Pad2)") (class "Default")
      (node (ref "C17") (pin "2") (pinfunction "2_2") (pintype "passive"))
      (node (ref "R54") (pin "1") (pinfunction "1_1") (pintype "passive"))
    )
    (net (code "53") (name "Net-(C46-Pad2)") (class "Default")
      (node (ref "C46") (pin "2") (pinfunction "2_2") (pintype "passive"))
      (node (ref "R59") (pin "1") (pinfunction "1_1") (pintype "passive"))
      (node (ref "R60") (pin "2") (pinfunction "2_2") (pintype "passive"))
      (node (ref "R61") (pin "2") (pinfunction "2_2") (pintype "passive"))
    )
    (net (code "54") (name "Net-(SW2-A_IN)") (class "Default")
      (node (ref "R55") (pin "1") (pinfunction "1_1") (pintype "passive"))
      (node (ref "SW2") (pin "2") (pinfunction "A_IN_2") (pintype "passive"))
    )
    (net (code "55") (name "Net-(SW2-A_OUT2)") (class "Default")
      (node (ref "SW2") (pin "3") (pinfunction "A_OUT2_3") (pintype "passive"))
      (node (ref "U13") (pin "1") (pinfunction "OUTA_1") (pintype "passive"))
      (node (ref "U13") (pin "2") (pinfunction "-A_2") (pintype "passive"))
    )
    (net (code "56") (name "Net-(SW2-B_IN)") (class "Default")
      (node (ref "R56") (pin "1") (pinfunction "1_1") (pintype "passive"))
      (node (ref "SW2") (pin "5") (pinfunction "B_IN_5") (pintype "passive"))
    )
    (net (code "57") (name "Net-(SW2-B_IN2)") (class "Default")
      (node (ref "SW2") (pin "6") (pinfunction "B_IN2_6") (pintype "passive"))
      (node (ref "U13") (pin "6") (pinfunction "-B_6") (pintype "passive"))
      (node (ref "U13") (pin "7") (pinfunction "OUTB_7") (pintype "passive"))
    )
    (net (code "58") (name "Net-(SW3-A_IN)") (class "Default")
      (node (ref "R57") (pin "1") (pinfunction "1_1") (pintype "passive"))
      (node (ref "SW3") (pin "2") (pinfunction "A_IN_2") (pintype "passive"))
    )
    (net (code "59") (name "Net-(SW3-A_OUT2)") (class "Default")
      (node (ref "SW3") (pin "3") (pinfunction "A_OUT2_3") (pintype "passive"))
      (node (ref "U13") (pin "10") (pinfunction "OUTC_10") (pintype "passive"))
      (node (ref "U13") (pin "11") (pinfunction "-C_11") (pintype "passive"))
    )
    (net (code "60") (name "Net-(SW3-B_IN)") (class "Default")
      (node (ref "R58") (pin "1") (pinfunction "1_1") (pintype "passive"))
      (node (ref "SW3") (pin "5") (pinfunction "B_IN_5") (pintype "passive"))
    )
    (net (code "61") (name "Net-(SW3-B_IN2)") (class "Default")
      (node (ref "SW3") (pin "6") (pinfunction "B_IN2_6") (pintype "passive"))
      (node (ref "U13") (pin "15") (pinfunction "-D_15") (pintype "passive"))
      (node (ref "U13") (pin "16") (pinfunction "OUTD_16") (pintype "passive"))
    )
    (net (code "62") (name "Net-(U1C-VREFHIA)") (class "Default")
      (node (ref "R51") (pin "2") (pinfunction "2_2") (pintype "passive"))
      (node (ref "R55") (pin "2") (pinfunction "2_2") (pintype "passive"))
      (node (ref "U1") (pin "V1") (pinfunction "VREFHIA_V1") (pintype "bidirectional"))
    )
    (net (code "63") (name "Net-(U1C-VREFHIB)") (class "Default")
      (node (ref "R52") (pin "2") (pinfunction "2_2") (pintype "passive"))
      (node (ref "R56") (pin "2") (pinfunction "2_2") (pintype "passive"))
      (node (ref "U1") (pin "W5") (pinfunction "VREFHIB_W5") (pintype "bidirectional"))
    )
    (net (code "64") (name "Net-(U1C-VREFHIC)") (class "Default")
      (node (ref "R53") (pin "2") (pinfunction "2_2") (pintype "passive"))
      (node (ref "R57") (pin "2") (pinfunction "2_2") (pintype "passive"))
      (node (ref "U1") (pin "R1") (pinfunction "VREFHIC_R1") (pintype "bidirectional"))
    )
    (net (code "65") (name "Net-(U1C-VREFHID)") (class "Default")
      (node (ref "R54") (pin "2") (pinfunction "2_2") (pintype "passive"))
      (node (ref "R58") (pin "2") (pinfunction "2_2") (pintype "passive"))
      (node (ref "U1") (pin "V5") (pinfunction "VREFHID_V5") (pintype "bidirectional"))
    )
    (net (code "66") (name "Net-(U12-TRIM{slash}NR)") (class "Default")
      (node (ref "C45") (pin "2") (pinfunction "2_2") (pintype "passive"))
      (node (ref "U12") (pin "5") (pinfunction "TRIM/NR_5") (pintype "passive"))
    )
    (net (code "67") (name "Net-(U12-VOUT)") (class "Default")
      (node (ref "R60") (pin "1") (pinfunction "1_1") (pintype "passive"))
      (node (ref "U12") (pin "6") (pinfunction "VOUT_6") (pintype "passive"))
    )
    (net (code "68") (name "Net-(U13A-+A)") (class "Default")
      (node (ref "C47") (pin "2") (pinfunction "2_2") (pintype "passive"))
      (node (ref "R61") (pin "1") (pinfunction "1_1") (pintype "passive"))
      (node (ref "U13") (pin "12") (pinfunction "+C_12") (pintype "passive"))
      (node (ref "U13") (pin "14") (pinfunction "+D_14") (pintype "passive"))
      (node (ref "U13") (pin "3") (pinfunction "+A_3") (pintype "passive"))
      (node (ref "U13") (pin "5") (pinfunction "+B_5") (pintype "passive"))
    )
    (net (code "69") (name "VDDA_MCU_3V3") (class "Default")
      (node (ref "C10") (pin "2") (pinfunction "2_2") (pintype "passive"))
      (node (ref "C11") (pin "2") (pinfunction "2_2") (pintype "passive"))
      (node (ref "C12") (pin "2") (pinfunction "2_2") (pintype "passive"))
      (node (ref "C13") (pin "2") (pinfunction "2_2") (pintype "passive"))
      (node (ref "C42") (pin "1") (pinfunction "1_1") (pintype "passive"))
      (node (ref "C43") (pin "1") (pinfunction "1_1") (pintype "passive"))
      (node (ref "C44") (pin "2") (pinfunction "2_2") (pintype "passive"))
      (node (ref "C9") (pin "2") (pinfunction "2_2") (pintype "passive"))
      (node (ref "SW2") (pin "1") (pinfunction "A_OUT1_1") (pintype "passive"))
      (node (ref "SW2") (pin "4") (pinfunction "B_IN1_4") (pintype "passive"))
      (node (ref "SW3") (pin "1") (pinfunction "A_OUT1_1") (pintype "passive"))
      (node (ref "SW3") (pin "4") (pinfunction "B_IN1_4") (pintype "passive"))
      (node (ref "U1") (pin "P6") (pinfunction "VDDA_P6") (pintype "power_in"))
      (node (ref "U1") (pin "R6") (pinfunction "VDDA_R6") (pintype "power_in"))
      (node (ref "U10") (pin "5") (pinfunction "VP_5") (pintype "power_in"))
      (node (ref "U11") (pin "5") (pinfunction "VP_5") (pintype "power_in"))
      (node (ref "U12") (pin "2") (pinfunction "VIN_2") (pintype "passive"))
      (node (ref "U13") (pin "4") (pinfunction "V+_4") (pintype "passive"))
      (node (ref "U6") (pin "5") (pinfunction "VP_5") (pintype "power_in"))
      (node (ref "U7") (pin "5") (pinfunction "VP_5") (pintype "power_in"))
      (node (ref "U8") (pin "5") (pinfunction "VP_5") (pintype "power_in"))
      (node (ref "U9") (pin "5") (pinfunction "VP_5") (pintype "power_in"))
    )
    (net (code "70") (name "unconnected-(U12-DNC-Pad1)") (class "Default")
      (node (ref "U12") (pin "1") (pinfunction "DNC_1") (pintype "passive"))
    )
    (net (code "71") (name "unconnected-(U12-DNC-Pad8)") (class "Default")
      (node (ref "U12") (pin "8") (pinfunction "DNC_8") (pintype "passive"))
    )
    (net (code "72") (name "unconnected-(U12-NC-Pad7)") (class "Default")
      (node (ref "U12") (pin "7") (pinfunction "NC_7") (pintype "passive"))
    )
    (net (code "73") (name "unconnected-(U12-TEMP-Pad3)") (class "Default")
      (node (ref "U12") (pin "3") (pinfunction "TEMP_3") (pintype "passive"))
    )
    (net (code "74") (name "unconnected-(U13E-NC-Pad8)") (class "Default")
      (node (ref "U13") (pin "8") (pinfunction "NC_8") (pintype "passive"))
    )
    (net (code "75") (name "unconnected-(U13E-NC-Pad9)") (class "Default")
      (node (ref "U13") (pin "9") (pinfunction "NC_9") (pintype "passive"))
    )
  )
)
